# pixel.net
KiCad netlist of a schematic drawn in EAGLE
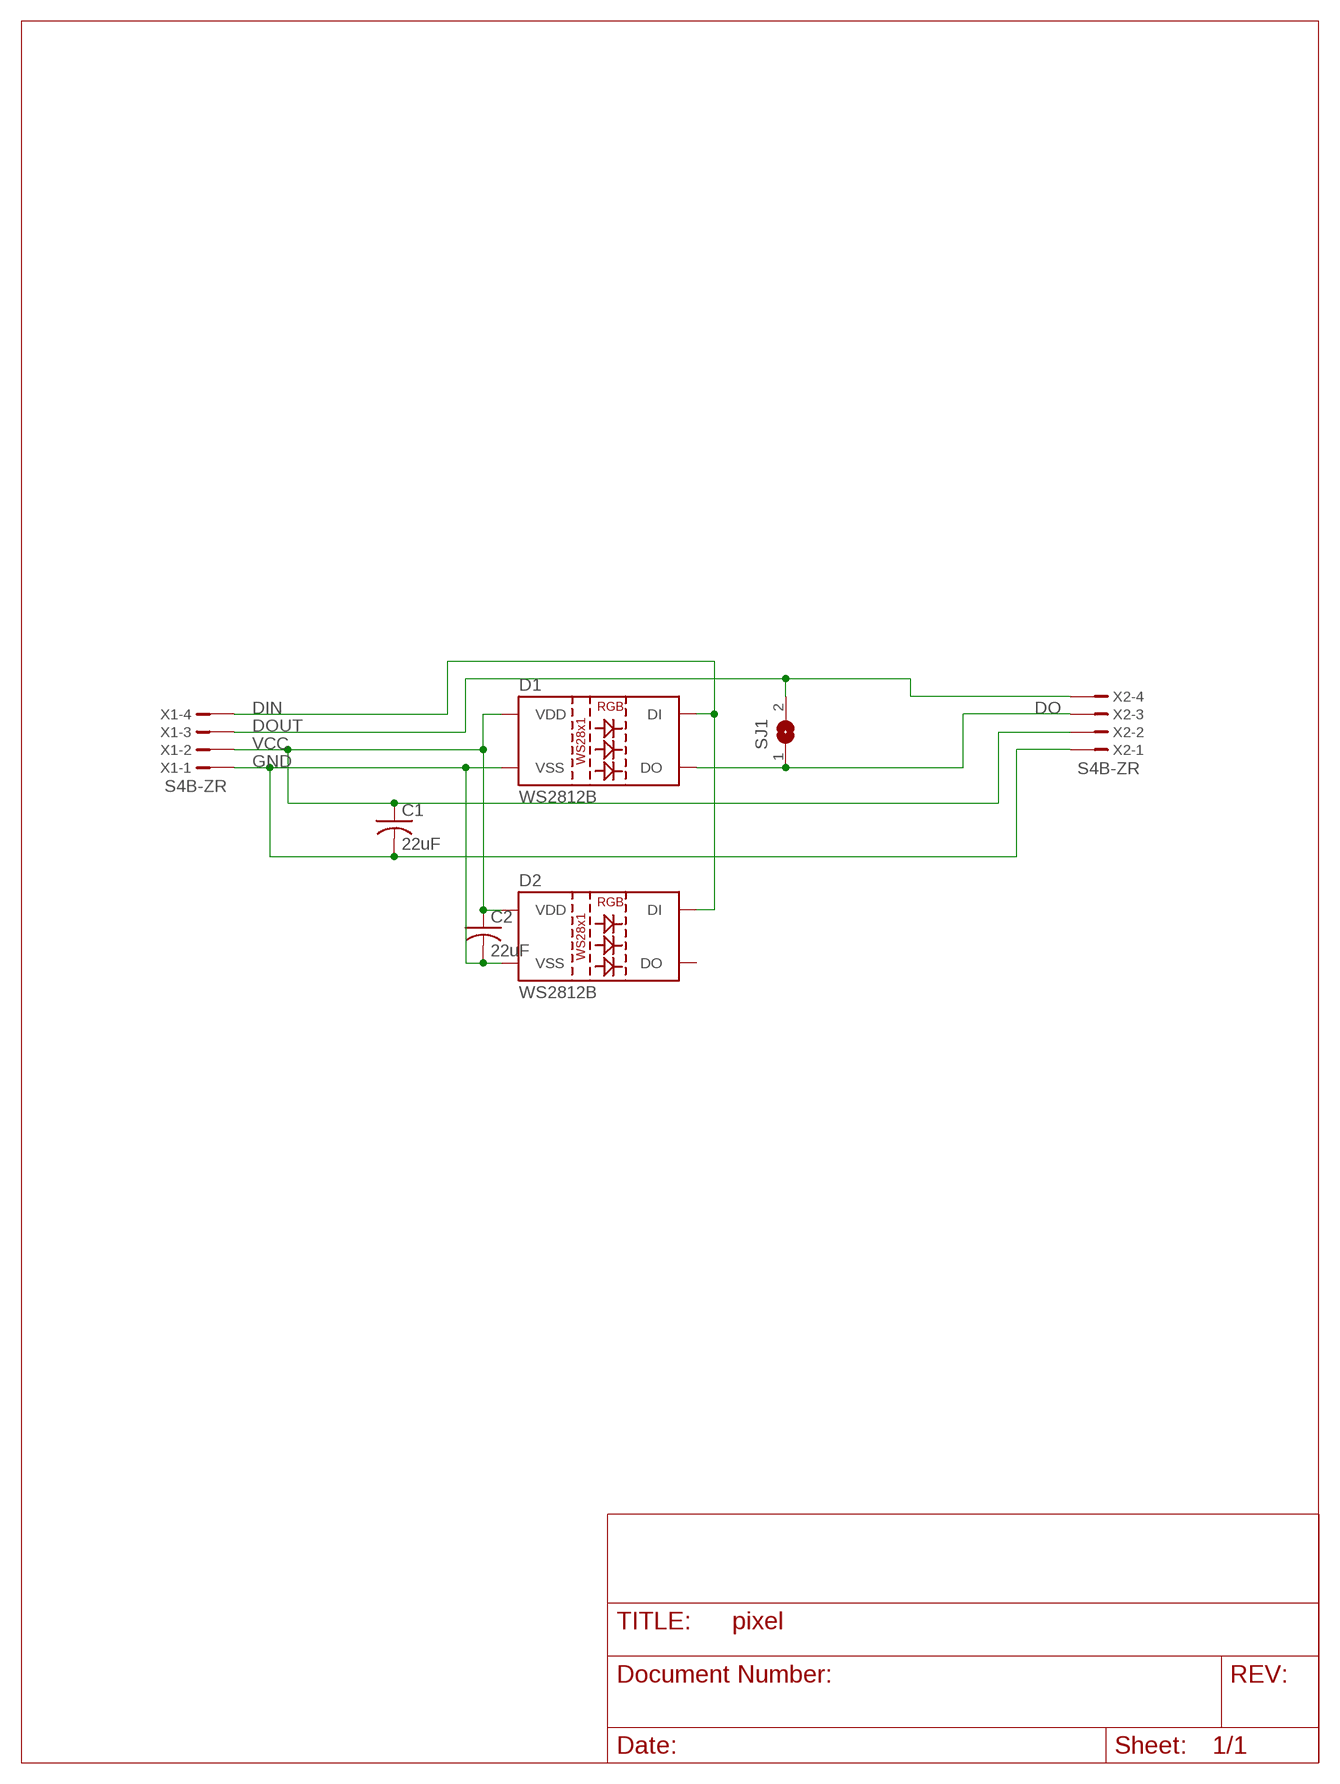
[diagram p0: schematic, sheet 1]

(export (version "E")
  (design (tool "Eeschema 10.0.6"))
  (components
    (comp (ref "C1")
      (value "22uF")
      (footprint "eagle-import:C0402")
      (libsource (lib "eagle-import") (part "C-USC0402"))
    )
    (comp (ref "C2")
      (value "22uF")
      (footprint "eagle-import:C0402")
      (libsource (lib "eagle-import") (part "C-USC0402"))
    )
    (comp (ref "D1")
      (value "WS2812B")
      (footprint "eagle-import:WS2812B")
      (libsource (lib "eagle-import") (part "WS2812B"))
    )
    (comp (ref "D2")
      (value "WS2812B")
      (footprint "eagle-import:WS2812B")
      (libsource (lib "eagle-import") (part "WS2812B"))
    )
    (comp (ref "SJ1") (value "SJ") (footprint "eagle-import:SJ") (libsource (lib "eagle-import") (part "SJ")))
    (comp (ref "X1")
      (value "S4B-ZR")
      (footprint "eagle-import:S4B-ZR")
      (fields (field (name "MF") "FARNELL") (field (name "MPN") "S4B-ZR(LF)(SN)"))
      (libsource (lib "eagle-import") (part "?4B-ZRS"))
    )
    (comp (ref "X2")
      (value "S4B-ZR")
      (footprint "eagle-import:S4B-ZR")
      (fields (field (name "MF") "FARNELL") (field (name "MPN") "S4B-ZR(LF)(SN)"))
      (libsource (lib "eagle-import") (part "?4B-ZRS"))
    )
  )
  (nets
    (net (code "1") (name "/DIN") (class "Default")
      (node (ref "D1") (pin "4") (pinfunction "DI_4") (pintype "bidirectional"))
      (node (ref "D2") (pin "4") (pinfunction "DI_4") (pintype "bidirectional"))
      (node (ref "X1") (pin "4") (pinfunction "1_4") (pintype "passive"))
    )
    (net (code "2") (name "/DO") (class "Default")
      (node (ref "D1") (pin "2") (pinfunction "DO_2") (pintype "bidirectional"))
      (node (ref "SJ1") (pin "1") (pinfunction "1_1") (pintype "passive"))
      (node (ref "X2") (pin "3") (pinfunction "1_3") (pintype "passive"))
    )
    (net (code "3") (name "/DOUT") (class "Default")
      (node (ref "SJ1") (pin "2") (pinfunction "2_2") (pintype "passive"))
      (node (ref "X1") (pin "3") (pinfunction "1_3") (pintype "passive"))
      (node (ref "X2") (pin "4") (pinfunction "1_4") (pintype "passive"))
    )
    (net (code "4") (name "/GND") (class "Default")
      (node (ref "C1") (pin "2") (pinfunction "2_2") (pintype "passive"))
      (node (ref "C2") (pin "2") (pinfunction "2_2") (pintype "passive"))
      (node (ref "D1") (pin "3") (pinfunction "VSS_3") (pintype "bidirectional"))
      (node (ref "D2") (pin "3") (pinfunction "VSS_3") (pintype "bidirectional"))
      (node (ref "X1") (pin "1") (pinfunction "1_1") (pintype "passive"))
      (node (ref "X2") (pin "1") (pinfunction "1_1") (pintype "passive"))
    )
    (net (code "5") (name "/VCC") (class "Default")
      (node (ref "C1") (pin "1") (pinfunction "1_1") (pintype "passive"))
      (node (ref "C2") (pin "1") (pinfunction "1_1") (pintype "passive"))
      (node (ref "D1") (pin "1") (pinfunction "VDD_1") (pintype "bidirectional"))
      (node (ref "D2") (pin "1") (pinfunction "VDD_1") (pintype "bidirectional"))
      (node (ref "X1") (pin "2") (pinfunction "1_2") (pintype "passive"))
      (node (ref "X2") (pin "2") (pinfunction "1_2") (pintype "passive"))
    )
    (net (code "6") (name "unconnected-(D2-DO-Pad2)") (class "Default")
      (node (ref "D2") (pin "2") (pinfunction "DO_2") (pintype "bidirectional"))
    )
  )
)
